# 1nuc_sluyba.net
KiCad netlist of a schematic drawn in EAGLE
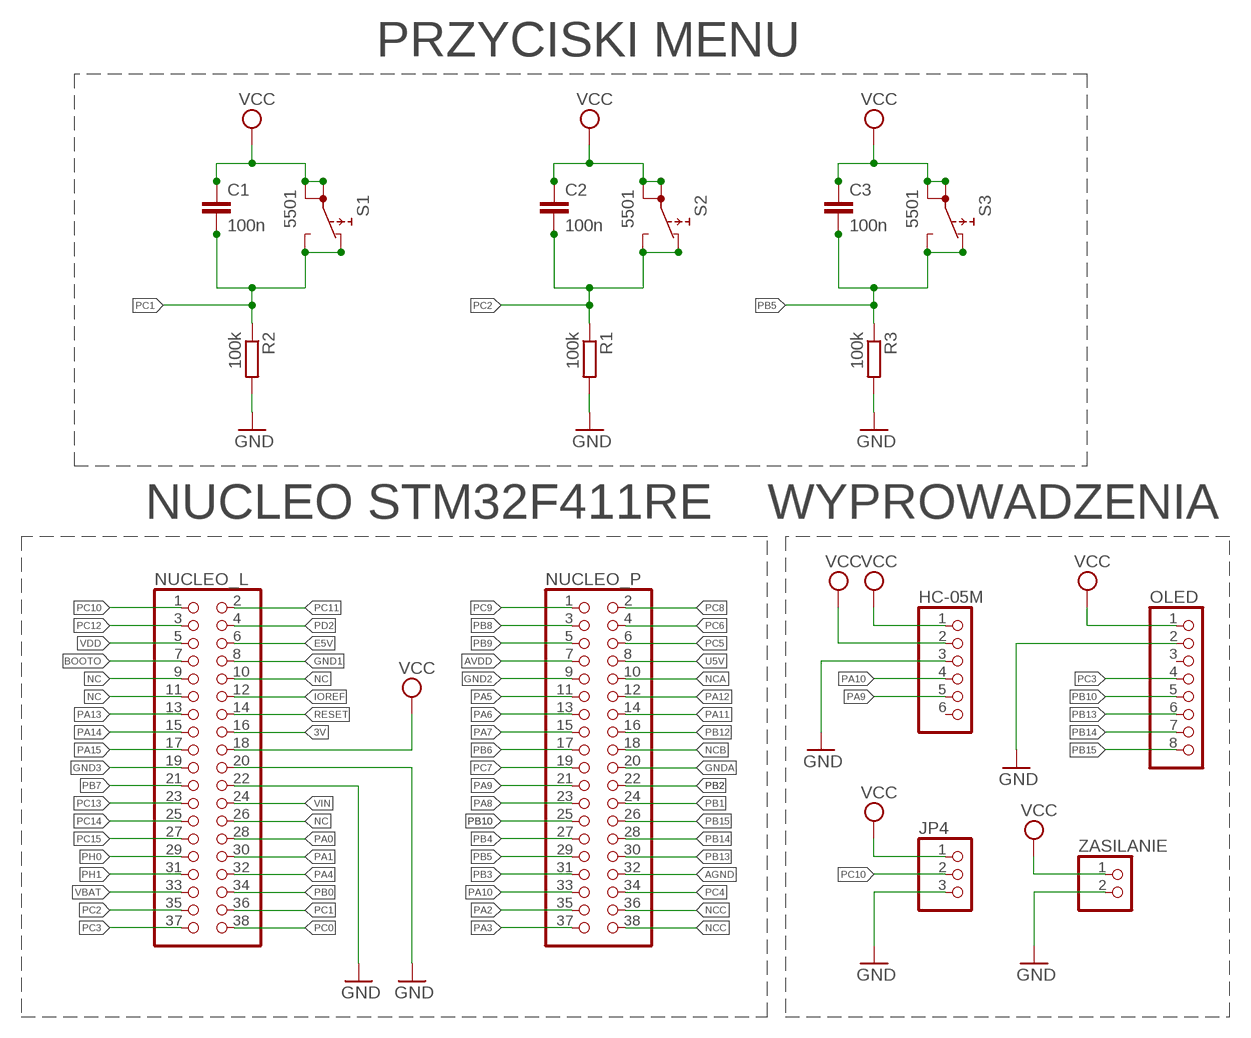
[diagram p0: schematic, sheet 1]

(export (version "E")
  (design (tool "Eeschema 10.0.6"))
  (components
    (comp (ref "C1")
      (value "100n")
      (footprint "eagle-import:C1206")
      (libsource (lib "eagle-import") (part "C-EUC1206"))
    )
    (comp (ref "C2")
      (value "100n")
      (footprint "eagle-import:C1206")
      (libsource (lib "eagle-import") (part "C-EUC1206"))
    )
    (comp (ref "C3")
      (value "100n")
      (footprint "eagle-import:C1206")
      (libsource (lib "eagle-import") (part "C-EUC1206"))
    )
    (comp (ref "HC-05M")
      (value "PINHD-1X6")
      (footprint "eagle-import:1X06")
      (libsource (lib "eagle-import") (part "PINHD-1X6"))
    )
    (comp (ref "JP4")
      (value "PINHD-1X3")
      (footprint "eagle-import:1X03")
      (libsource (lib "eagle-import") (part "PINHD-1X3"))
    )
    (comp (ref "NUCLEO_L")
      (value "PINHD-2X19")
      (footprint "eagle-import:2X19")
      (libsource (lib "eagle-import") (part "PINHD-2X19"))
    )
    (comp (ref "NUCLEO_P")
      (value "PINHD-2X19")
      (footprint "eagle-import:2X19")
      (libsource (lib "eagle-import") (part "PINHD-2X19"))
    )
    (comp (ref "OLED")
      (value "PINHD-1X8")
      (footprint "eagle-import:1X08")
      (libsource (lib "eagle-import") (part "PINHD-1X8"))
    )
    (comp (ref "R1")
      (value "100k")
      (footprint "eagle-import:R0805")
      (libsource (lib "eagle-import") (part "R-EU_R0805"))
    )
    (comp (ref "R2")
      (value "100k")
      (footprint "eagle-import:R0805")
      (libsource (lib "eagle-import") (part "R-EU_R0805"))
    )
    (comp (ref "R3")
      (value "100k")
      (footprint "eagle-import:R0805")
      (libsource (lib "eagle-import") (part "R-EU_R0805"))
    )
    (comp (ref "S1")
      (value "5501")
      (footprint "eagle-import:5501")
      (libsource (lib "eagle-import") (part "55?01"))
    )
    (comp (ref "S2")
      (value "5501")
      (footprint "eagle-import:5501")
      (libsource (lib "eagle-import") (part "55?01"))
    )
    (comp (ref "S3")
      (value "5501")
      (footprint "eagle-import:5501")
      (libsource (lib "eagle-import") (part "55?01"))
    )
    (comp (ref "ZASILANIE")
      (value "PINHD-1X2")
      (footprint "eagle-import:1X02")
      (libsource (lib "eagle-import") (part "PINHD-1X2"))
    )
  )
  (nets
    (net (code "1") (name "3V") (class "Default")
      (node (ref "NUCLEO_L") (pin "16") (pinfunction "16_16") (pintype "passive"))
    )
    (net (code "2") (name "AGND") (class "Default")
      (node (ref "NUCLEO_P") (pin "32") (pinfunction "32_32") (pintype "passive"))
    )
    (net (code "3") (name "AVDD") (class "Default")
      (node (ref "NUCLEO_P") (pin "7") (pinfunction "7_7") (pintype "passive"))
    )
    (net (code "4") (name "BOOTO") (class "Default")
      (node (ref "NUCLEO_L") (pin "7") (pinfunction "7_7") (pintype "passive"))
    )
    (net (code "5") (name "E5V") (class "Default")
      (node (ref "NUCLEO_L") (pin "6") (pinfunction "6_6") (pintype "passive"))
    )
    (net (code "6") (name "GND") (class "Default")
      (node (ref "HC-05M") (pin "3") (pinfunction "3_3") (pintype "passive"))
      (node (ref "JP4") (pin "3") (pinfunction "3_3") (pintype "passive"))
      (node (ref "NUCLEO_L") (pin "20") (pinfunction "20_20") (pintype "passive"))
      (node (ref "NUCLEO_L") (pin "22") (pinfunction "22_22") (pintype "passive"))
      (node (ref "OLED") (pin "2") (pinfunction "2_2") (pintype "passive"))
      (node (ref "R1") (pin "2") (pinfunction "2_2") (pintype "passive"))
      (node (ref "R2") (pin "2") (pinfunction "2_2") (pintype "passive"))
      (node (ref "R3") (pin "2") (pinfunction "2_2") (pintype "passive"))
      (node (ref "ZASILANIE") (pin "2") (pinfunction "2_2") (pintype "passive"))
    )
    (net (code "7") (name "GND1") (class "Default")
      (node (ref "NUCLEO_L") (pin "8") (pinfunction "8_8") (pintype "passive"))
    )
    (net (code "8") (name "GND2") (class "Default")
      (node (ref "NUCLEO_P") (pin "9") (pinfunction "9_9") (pintype "passive"))
    )
    (net (code "9") (name "GND3") (class "Default")
      (node (ref "NUCLEO_L") (pin "19") (pinfunction "19_19") (pintype "passive"))
    )
    (net (code "10") (name "GNDA") (class "Default")
      (node (ref "NUCLEO_P") (pin "20") (pinfunction "20_20") (pintype "passive"))
    )
    (net (code "11") (name "IOREF") (class "Default")
      (node (ref "NUCLEO_L") (pin "12") (pinfunction "12_12") (pintype "passive"))
    )
    (net (code "12") (name "NC") (class "Default")
      (node (ref "NUCLEO_L") (pin "10") (pinfunction "10_10") (pintype "passive"))
      (node (ref "NUCLEO_L") (pin "11") (pinfunction "11_11") (pintype "passive"))
      (node (ref "NUCLEO_L") (pin "26") (pinfunction "26_26") (pintype "passive"))
      (node (ref "NUCLEO_L") (pin "9") (pinfunction "9_9") (pintype "passive"))
    )
    (net (code "13") (name "NCA") (class "Default")
      (node (ref "NUCLEO_P") (pin "10") (pinfunction "10_10") (pintype "passive"))
    )
    (net (code "14") (name "NCB") (class "Default")
      (node (ref "NUCLEO_P") (pin "18") (pinfunction "18_18") (pintype "passive"))
    )
    (net (code "15") (name "NCC") (class "Default")
      (node (ref "NUCLEO_P") (pin "36") (pinfunction "36_36") (pintype "passive"))
      (node (ref "NUCLEO_P") (pin "38") (pinfunction "38_38") (pintype "passive"))
    )
    (net (code "16") (name "PA0") (class "Default")
      (node (ref "NUCLEO_L") (pin "28") (pinfunction "28_28") (pintype "passive"))
    )
    (net (code "17") (name "PA1") (class "Default")
      (node (ref "NUCLEO_L") (pin "30") (pinfunction "30_30") (pintype "passive"))
    )
    (net (code "18") (name "PA2") (class "Default")
      (node (ref "NUCLEO_P") (pin "35") (pinfunction "35_35") (pintype "passive"))
    )
    (net (code "19") (name "PA3") (class "Default")
      (node (ref "NUCLEO_P") (pin "37") (pinfunction "37_37") (pintype "passive"))
    )
    (net (code "20") (name "PA4") (class "Default")
      (node (ref "NUCLEO_L") (pin "32") (pinfunction "32_32") (pintype "passive"))
    )
    (net (code "21") (name "PA5") (class "Default")
      (node (ref "NUCLEO_P") (pin "11") (pinfunction "11_11") (pintype "passive"))
    )
    (net (code "22") (name "PA6") (class "Default")
      (node (ref "NUCLEO_P") (pin "13") (pinfunction "13_13") (pintype "passive"))
    )
    (net (code "23") (name "PA7") (class "Default")
      (node (ref "NUCLEO_P") (pin "15") (pinfunction "15_15") (pintype "passive"))
    )
    (net (code "24") (name "PA8") (class "Default")
      (node (ref "NUCLEO_P") (pin "23") (pinfunction "23_23") (pintype "passive"))
    )
    (net (code "25") (name "PA9") (class "Default")
      (node (ref "HC-05M") (pin "5") (pinfunction "5_5") (pintype "passive"))
      (node (ref "NUCLEO_P") (pin "21") (pinfunction "21_21") (pintype "passive"))
    )
    (net (code "26") (name "PA10") (class "Default")
      (node (ref "HC-05M") (pin "4") (pinfunction "4_4") (pintype "passive"))
      (node (ref "NUCLEO_P") (pin "33") (pinfunction "33_33") (pintype "passive"))
    )
    (net (code "27") (name "PA11") (class "Default")
      (node (ref "NUCLEO_P") (pin "14") (pinfunction "14_14") (pintype "passive"))
    )
    (net (code "28") (name "PA12") (class "Default")
      (node (ref "NUCLEO_P") (pin "12") (pinfunction "12_12") (pintype "passive"))
    )
    (net (code "29") (name "PA13") (class "Default")
      (node (ref "NUCLEO_L") (pin "13") (pinfunction "13_13") (pintype "passive"))
    )
    (net (code "30") (name "PA14") (class "Default")
      (node (ref "NUCLEO_L") (pin "15") (pinfunction "15_15") (pintype "passive"))
    )
    (net (code "31") (name "PA15") (class "Default")
      (node (ref "NUCLEO_L") (pin "17") (pinfunction "17_17") (pintype "passive"))
    )
    (net (code "32") (name "PB0") (class "Default")
      (node (ref "NUCLEO_L") (pin "34") (pinfunction "34_34") (pintype "passive"))
    )
    (net (code "33") (name "PB1") (class "Default")
      (node (ref "NUCLEO_P") (pin "24") (pinfunction "24_24") (pintype "passive"))
    )
    (net (code "34") (name "PB2") (class "Default")
      (node (ref "NUCLEO_P") (pin "22") (pinfunction "22_22") (pintype "passive"))
    )
    (net (code "35") (name "PB3") (class "Default")
      (node (ref "NUCLEO_P") (pin "31") (pinfunction "31_31") (pintype "passive"))
    )
    (net (code "36") (name "PB4") (class "Default")
      (node (ref "NUCLEO_P") (pin "27") (pinfunction "27_27") (pintype "passive"))
    )
    (net (code "37") (name "PB5") (class "Default")
      (node (ref "C3") (pin "2") (pinfunction "2_2") (pintype "passive"))
      (node (ref "NUCLEO_P") (pin "29") (pinfunction "29_29") (pintype "passive"))
      (node (ref "R3") (pin "1") (pinfunction "1_1") (pintype "passive"))
      (node (ref "S3") (pin "NC") (pinfunction "NC_NC") (pintype "passive"))
      (node (ref "S3") (pin "NO") (pinfunction "NO_NO") (pintype "passive"))
    )
    (net (code "38") (name "PB6") (class "Default")
      (node (ref "NUCLEO_P") (pin "17") (pinfunction "17_17") (pintype "passive"))
    )
    (net (code "39") (name "PB7") (class "Default")
      (node (ref "NUCLEO_L") (pin "21") (pinfunction "21_21") (pintype "passive"))
    )
    (net (code "40") (name "PB8") (class "Default")
      (node (ref "NUCLEO_P") (pin "3") (pinfunction "3_3") (pintype "passive"))
    )
    (net (code "41") (name "PB9") (class "Default")
      (node (ref "NUCLEO_P") (pin "5") (pinfunction "5_5") (pintype "passive"))
    )
    (net (code "42") (name "PB10") (class "Default")
      (node (ref "NUCLEO_P") (pin "25") (pinfunction "25_25") (pintype "passive"))
      (node (ref "OLED") (pin "5") (pinfunction "5_5") (pintype "passive"))
    )
    (net (code "43") (name "PB12") (class "Default")
      (node (ref "NUCLEO_P") (pin "16") (pinfunction "16_16") (pintype "passive"))
    )
    (net (code "44") (name "PB13") (class "Default")
      (node (ref "NUCLEO_P") (pin "30") (pinfunction "30_30") (pintype "passive"))
      (node (ref "OLED") (pin "6") (pinfunction "6_6") (pintype "passive"))
    )
    (net (code "45") (name "PB14") (class "Default")
      (node (ref "NUCLEO_P") (pin "28") (pinfunction "28_28") (pintype "passive"))
      (node (ref "OLED") (pin "7") (pinfunction "7_7") (pintype "passive"))
    )
    (net (code "46") (name "PB15") (class "Default")
      (node (ref "NUCLEO_P") (pin "26") (pinfunction "26_26") (pintype "passive"))
      (node (ref "OLED") (pin "8") (pinfunction "8_8") (pintype "passive"))
    )
    (net (code "47") (name "PC0") (class "Default")
      (node (ref "NUCLEO_L") (pin "38") (pinfunction "38_38") (pintype "passive"))
    )
    (net (code "48") (name "PC1") (class "Default")
      (node (ref "C1") (pin "2") (pinfunction "2_2") (pintype "passive"))
      (node (ref "NUCLEO_L") (pin "36") (pinfunction "36_36") (pintype "passive"))
      (node (ref "R2") (pin "1") (pinfunction "1_1") (pintype "passive"))
      (node (ref "S1") (pin "NC") (pinfunction "NC_NC") (pintype "passive"))
      (node (ref "S1") (pin "NO") (pinfunction "NO_NO") (pintype "passive"))
    )
    (net (code "49") (name "PC2") (class "Default")
      (node (ref "C2") (pin "2") (pinfunction "2_2") (pintype "passive"))
      (node (ref "NUCLEO_L") (pin "35") (pinfunction "35_35") (pintype "passive"))
      (node (ref "R1") (pin "1") (pinfunction "1_1") (pintype "passive"))
      (node (ref "S2") (pin "NC") (pinfunction "NC_NC") (pintype "passive"))
      (node (ref "S2") (pin "NO") (pinfunction "NO_NO") (pintype "passive"))
    )
    (net (code "50") (name "PC3") (class "Default")
      (node (ref "NUCLEO_L") (pin "37") (pinfunction "37_37") (pintype "passive"))
      (node (ref "OLED") (pin "4") (pinfunction "4_4") (pintype "passive"))
    )
    (net (code "51") (name "PC4") (class "Default")
      (node (ref "NUCLEO_P") (pin "34") (pinfunction "34_34") (pintype "passive"))
    )
    (net (code "52") (name "PC5") (class "Default")
      (node (ref "NUCLEO_P") (pin "6") (pinfunction "6_6") (pintype "passive"))
    )
    (net (code "53") (name "PC6") (class "Default")
      (node (ref "NUCLEO_P") (pin "4") (pinfunction "4_4") (pintype "passive"))
    )
    (net (code "54") (name "PC7") (class "Default")
      (node (ref "NUCLEO_P") (pin "19") (pinfunction "19_19") (pintype "passive"))
    )
    (net (code "55") (name "PC8") (class "Default")
      (node (ref "NUCLEO_P") (pin "2") (pinfunction "2_2") (pintype "passive"))
    )
    (net (code "56") (name "PC9") (class "Default")
      (node (ref "NUCLEO_P") (pin "1") (pinfunction "1_1") (pintype "passive"))
    )
    (net (code "57") (name "PC10") (class "Default")
      (node (ref "JP4") (pin "2") (pinfunction "2_2") (pintype "passive"))
      (node (ref "NUCLEO_L") (pin "1") (pinfunction "1_1") (pintype "passive"))
    )
    (net (code "58") (name "PC11") (class "Default")
      (node (ref "NUCLEO_L") (pin "2") (pinfunction "2_2") (pintype "passive"))
    )
    (net (code "59") (name "PC12") (class "Default")
      (node (ref "NUCLEO_L") (pin "3") (pinfunction "3_3") (pintype "passive"))
    )
    (net (code "60") (name "PC13") (class "Default")
      (node (ref "NUCLEO_L") (pin "23") (pinfunction "23_23") (pintype "passive"))
    )
    (net (code "61") (name "PC14") (class "Default")
      (node (ref "NUCLEO_L") (pin "25") (pinfunction "25_25") (pintype "passive"))
    )
    (net (code "62") (name "PC15") (class "Default")
      (node (ref "NUCLEO_L") (pin "27") (pinfunction "27_27") (pintype "passive"))
    )
    (net (code "63") (name "PD2") (class "Default")
      (node (ref "NUCLEO_L") (pin "4") (pinfunction "4_4") (pintype "passive"))
    )
    (net (code "64") (name "PH0") (class "Default")
      (node (ref "NUCLEO_L") (pin "29") (pinfunction "29_29") (pintype "passive"))
    )
    (net (code "65") (name "PH1") (class "Default")
      (node (ref "NUCLEO_L") (pin "31") (pinfunction "31_31") (pintype "passive"))
    )
    (net (code "66") (name "RESET") (class "Default")
      (node (ref "NUCLEO_L") (pin "14") (pinfunction "14_14") (pintype "passive"))
    )
    (net (code "67") (name "U5V") (class "Default")
      (node (ref "NUCLEO_P") (pin "8") (pinfunction "8_8") (pintype "passive"))
    )
    (net (code "68") (name "VBAT") (class "Default")
      (node (ref "NUCLEO_L") (pin "33") (pinfunction "33_33") (pintype "passive"))
    )
    (net (code "69") (name "VCC") (class "Default")
      (node (ref "C1") (pin "1") (pinfunction "1_1") (pintype "passive"))
      (node (ref "C2") (pin "1") (pinfunction "1_1") (pintype "passive"))
      (node (ref "C3") (pin "1") (pinfunction "1_1") (pintype "passive"))
      (node (ref "HC-05M") (pin "1") (pinfunction "1_1") (pintype "passive"))
      (node (ref "HC-05M") (pin "2") (pinfunction "2_2") (pintype "passive"))
      (node (ref "JP4") (pin "1") (pinfunction "1_1") (pintype "passive"))
      (node (ref "NUCLEO_L") (pin "18") (pinfunction "18_18") (pintype "passive"))
      (node (ref "OLED") (pin "1") (pinfunction "1_1") (pintype "passive"))
      (node (ref "S1") (pin "1A") (pinfunction "1A_1A") (pintype "passive"))
      (node (ref "S1") (pin "1B") (pinfunction "1B_1B") (pintype "passive"))
      (node (ref "S2") (pin "1A") (pinfunction "1A_1A") (pintype "passive"))
      (node (ref "S2") (pin "1B") (pinfunction "1B_1B") (pintype "passive"))
      (node (ref "S3") (pin "1A") (pinfunction "1A_1A") (pintype "passive"))
      (node (ref "S3") (pin "1B") (pinfunction "1B_1B") (pintype "passive"))
      (node (ref "ZASILANIE") (pin "1") (pinfunction "1_1") (pintype "passive"))
    )
    (net (code "70") (name "VDD") (class "Default")
      (node (ref "NUCLEO_L") (pin "5") (pinfunction "5_5") (pintype "passive"))
    )
    (net (code "71") (name "VIN") (class "Default")
      (node (ref "NUCLEO_L") (pin "24") (pinfunction "24_24") (pintype "passive"))
    )
    (net (code "72") (name "unconnected-(HC-05M-Pad6)") (class "Default")
      (node (ref "HC-05M") (pin "6") (pinfunction "6_6") (pintype "passive"))
    )
    (net (code "73") (name "unconnected-(OLED-Pad3)") (class "Default")
      (node (ref "OLED") (pin "3") (pinfunction "3_3") (pintype "passive"))
    )
  )
)
